# implant_5_1.net
KiCad netlist of a schematic drawn in EAGLE
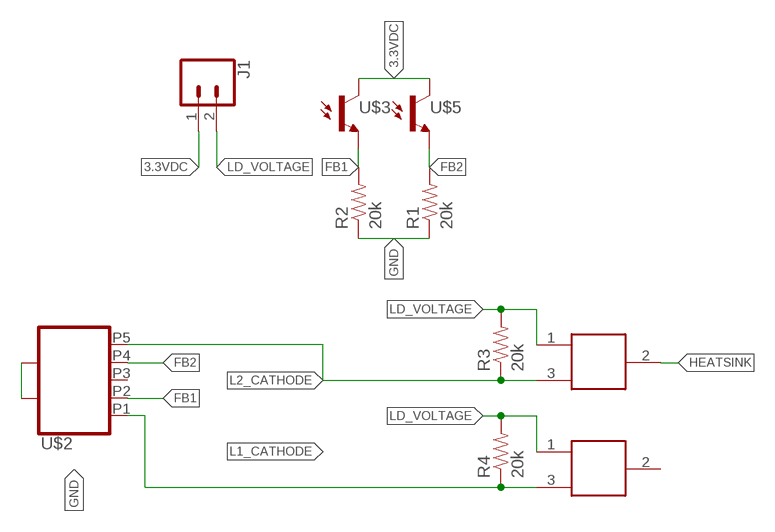
[diagram p0: schematic, sheet 1]

(export (version "E")
  (design (tool "Eeschema 10.0.6"))
  (components
    (comp (ref "J1")
      (value "CONN_02")
      (footprint "eagle-import:1X02")
      (libsource (lib "eagle-import") (part "CONN_02"))
    )
    (comp (ref "R1")
      (value "20k")
      (footprint "eagle-import:0805")
      (libsource (lib "eagle-import") (part "RESISTOR0805-RES"))
    )
    (comp (ref "R2")
      (value "20k")
      (footprint "eagle-import:0805")
      (libsource (lib "eagle-import") (part "RESISTOR0805-RES"))
    )
    (comp (ref "R3")
      (value "20k")
      (footprint "eagle-import:0805")
      (libsource (lib "eagle-import") (part "RESISTOR0805-RES"))
    )
    (comp (ref "R4")
      (value "20k")
      (footprint "eagle-import:0805")
      (libsource (lib "eagle-import") (part "RESISTOR0805-RES"))
    )
    (comp (ref "U$1")
      (value "LASERDIODE3.8MM")
      (footprint "eagle-import:LASERDIODE_3.8")
      (libsource (lib "eagle-import") (part "LASERDIODE3.8MM"))
    )
    (comp (ref "U$2")
      (value "USB_MICRO_SOCKET_VERT")
      (footprint "eagle-import:USB_VERT_MICRO_SMD")
      (libsource (lib "eagle-import") (part "USB_MICRO_SOCKET_VERT"))
    )
    (comp (ref "U$3")
      (value "AMBIENT-LIGHT-SENSOR")
      (footprint "eagle-import:PHOTO_PACK")
      (libsource (lib "eagle-import") (part "AMBIENT-LIGHT-SENSOR"))
    )
    (comp (ref "U$4")
      (value "LASERDIODE3.8MM")
      (footprint "eagle-import:LASERDIODE_3.8")
      (libsource (lib "eagle-import") (part "LASERDIODE3.8MM"))
    )
    (comp (ref "U$5")
      (value "AMBIENT-LIGHT-SENSOR")
      (footprint "eagle-import:PHOTO_PACK")
      (libsource (lib "eagle-import") (part "AMBIENT-LIGHT-SENSOR"))
    )
  )
  (nets
    (net (code "1") (name "3.3VDC") (class "Default")
      (node (ref "J1") (pin "1") (pinfunction "1_1") (pintype "passive"))
      (node (ref "U$3") (pin "COLLECTOR") (pinfunction "C_COLLECTOR") (pintype "passive"))
      (node (ref "U$5") (pin "COLLECTOR") (pinfunction "C_COLLECTOR") (pintype "passive"))
    )
    (net (code "2") (name "FB1") (class "Default")
      (node (ref "R2") (pin "2") (pinfunction "2_2") (pintype "passive"))
      (node (ref "U$2") (pin "P2") (pinfunction "P2_P2") (pintype "bidirectional"))
      (node (ref "U$3") (pin "EMITTER") (pinfunction "E_EMITTER") (pintype "passive"))
    )
    (net (code "3") (name "FB2") (class "Default")
      (node (ref "R1") (pin "2") (pinfunction "2_2") (pintype "passive"))
      (node (ref "U$2") (pin "P4") (pinfunction "P4_P4") (pintype "bidirectional"))
      (node (ref "U$5") (pin "EMITTER") (pinfunction "E_EMITTER") (pintype "passive"))
    )
    (net (code "4") (name "GND") (class "Default")
      (node (ref "R1") (pin "1") (pinfunction "1_1") (pintype "passive"))
      (node (ref "R2") (pin "1") (pinfunction "1_1") (pintype "passive"))
      (node (ref "U$2") (pin "P$1") (pinfunction "P$1_P$1") (pintype "bidirectional"))
      (node (ref "U$2") (pin "P$2") (pinfunction "P$2_P$2") (pintype "bidirectional"))
      (node (ref "U$2") (pin "P$3") (pinfunction "P$2_P$3") (pintype "bidirectional"))
    )
    (net (code "6") (name "HEATSINK") (class "Default")
      (node (ref "U$4") (pin "2") (pinfunction "2_2") (pintype "no_connect"))
    )
    (net (code "7") (name "L1_CATHODE") (class "Default")
      (node (ref "R4") (pin "1") (pinfunction "1_1") (pintype "passive"))
      (node (ref "U$1") (pin "3") (pinfunction "3_3") (pintype "bidirectional"))
      (node (ref "U$2") (pin "P1") (pinfunction "P1_P1") (pintype "bidirectional"))
    )
    (net (code "8") (name "L2_CATHODE") (class "Default")
      (node (ref "R3") (pin "1") (pinfunction "1_1") (pintype "passive"))
      (node (ref "U$2") (pin "P5") (pinfunction "P5_P5") (pintype "bidirectional"))
      (node (ref "U$4") (pin "3") (pinfunction "3_3") (pintype "bidirectional"))
    )
    (net (code "9") (name "LD_VOLTAGE") (class "Default")
      (node (ref "J1") (pin "2") (pinfunction "2_2") (pintype "passive"))
      (node (ref "R3") (pin "2") (pinfunction "2_2") (pintype "passive"))
      (node (ref "R4") (pin "2") (pinfunction "2_2") (pintype "passive"))
      (node (ref "U$1") (pin "1") (pinfunction "1_1") (pintype "bidirectional"))
      (node (ref "U$4") (pin "1") (pinfunction "1_1") (pintype "bidirectional"))
    )
    (net (code "10") (name "unconnected-(U$1-Pad2)") (class "Default")
      (node (ref "U$1") (pin "2") (pinfunction "2_2") (pintype "no_connect"))
    )
    (net (code "11") (name "unconnected-(U$2-PadP3)") (class "Default")
      (node (ref "U$2") (pin "P3") (pinfunction "P3_P3") (pintype "bidirectional"))
    )
  )
)
